# TRS_Jack_Breakout.net
KiCad netlist of a schematic drawn in EAGLE
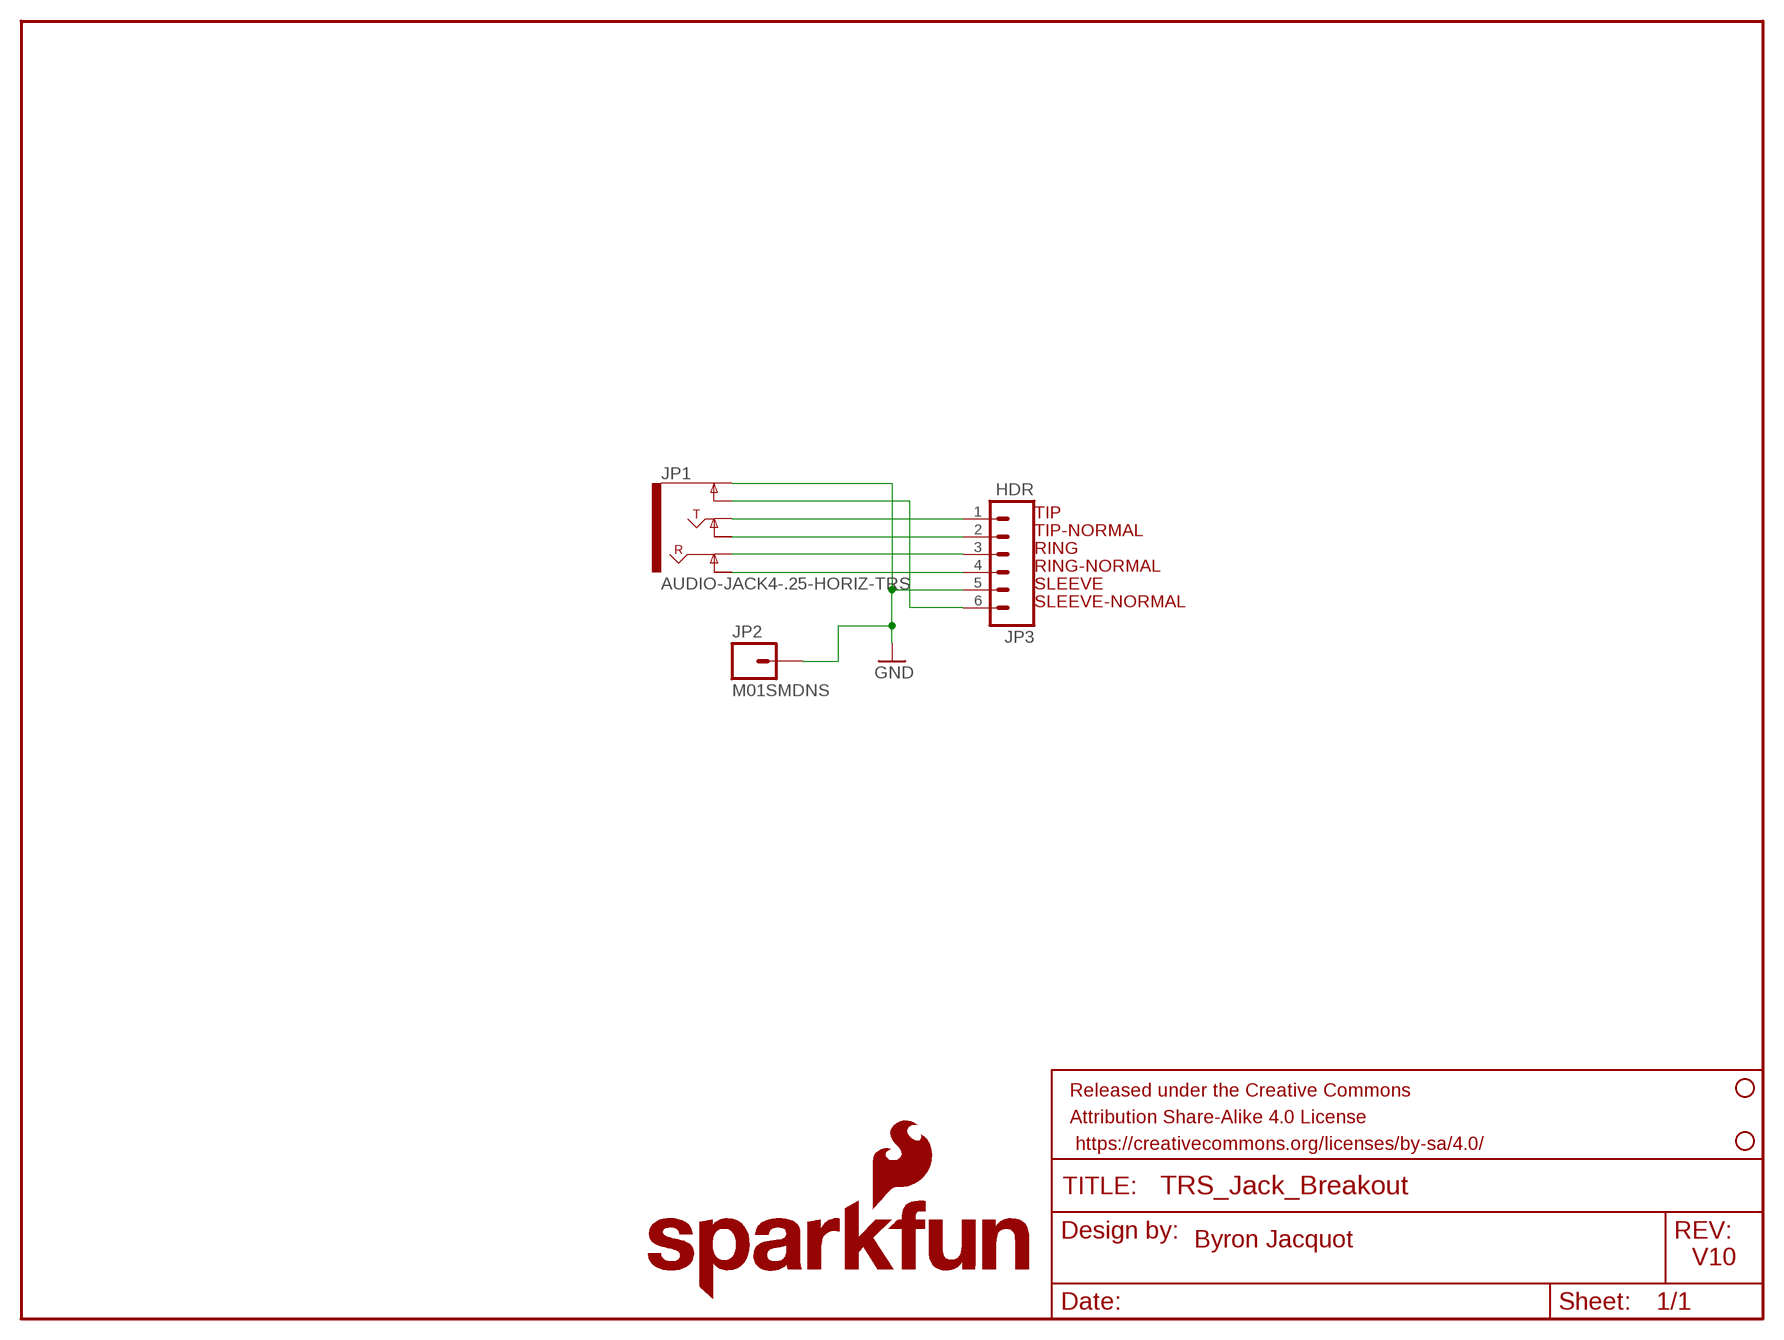
[diagram p0: schematic, sheet 1]

(export (version "E")
  (design (tool "Eeschema 10.0.6"))
  (components
    (comp (ref "FRAME1")
      (value "FRAME-LETTER")
      (footprint "eagle-import:CREATIVE_COMMONS")
      (libsource (lib "eagle-import") (part "FRAME-LETTER"))
    )
    (comp (ref "JP1")
      (value "AUDIO-JACK4-.25-HORIZ-TRS")
      (footprint "eagle-import:AUDIO-JACK-.25-INCH-HORIZ-PTH")
      (libsource (lib "eagle-import") (part "AUDIO-JACK4-.25-HORIZ-TRS"))
    )
    (comp (ref "JP2")
      (value "M01SMDNS")
      (footprint "eagle-import:1X01NS")
      (libsource (lib "eagle-import") (part "M01SMDNS"))
    )
    (comp (ref "JP3")
      (value "HDR")
      (footprint "eagle-import:1X06_NO_SILK")
      (libsource (lib "eagle-import") (part "M06NO_SILK"))
    )
    (comp (ref "LOGO1")
      (value "SFE_LOGO_NAME_FLAME.1_INCH")
      (footprint "eagle-import:SFE_LOGO_NAME_FLAME_.1")
      (libsource (lib "eagle-import") (part "SFE_LOGO_NAME_FLAME.1_INCH"))
    )
    (comp (ref "STANDOFF1")
      (value "STAND-OFF")
      (footprint "eagle-import:STAND-OFF")
      (libsource (lib "eagle-import") (part "STAND-OFF"))
    )
    (comp (ref "STANDOFF2")
      (value "STAND-OFF")
      (footprint "eagle-import:STAND-OFF")
      (libsource (lib "eagle-import") (part "STAND-OFF"))
    )
  )
  (nets
    (net (code "1") (name "GND") (class "Default")
      (node (ref "JP1") (pin "SLEEVE") (pinfunction "EARTH_SLEEVE") (pintype "bidirectional"))
      (node (ref "JP2") (pin "1") (pinfunction "1_1") (pintype "passive"))
      (node (ref "JP3") (pin "5") (pinfunction "5_5") (pintype "passive"))
    )
    (net (code "2") (name "Net-(JP1-EARTH-NORM)") (class "Default")
      (node (ref "JP1") (pin "SLEEVE-NORM") (pinfunction "EARTH-NORM_SLEEVE-NORM") (pintype "bidirectional"))
      (node (ref "JP3") (pin "6") (pinfunction "6_6") (pintype "passive"))
    )
    (net (code "3") (name "Net-(JP1-PadRING)") (class "Default")
      (node (ref "JP1") (pin "RING") (pinfunction "RING_RING") (pintype "bidirectional"))
      (node (ref "JP3") (pin "3") (pinfunction "3_3") (pintype "passive"))
    )
    (net (code "4") (name "Net-(JP1-PadRING-NORM)") (class "Default")
      (node (ref "JP1") (pin "RING-NORM") (pinfunction "RING-NORM_RING-NORM") (pintype "bidirectional"))
      (node (ref "JP3") (pin "4") (pinfunction "4_4") (pintype "passive"))
    )
    (net (code "5") (name "Net-(JP1-PadTIP)") (class "Default")
      (node (ref "JP1") (pin "TIP") (pinfunction "TIP_TIP") (pintype "bidirectional"))
      (node (ref "JP3") (pin "1") (pinfunction "1_1") (pintype "passive"))
    )
    (net (code "6") (name "Net-(JP1-PadTIP-NORM)") (class "Default")
      (node (ref "JP1") (pin "TIP-NORM") (pinfunction "TIP-NORM_TIP-NORM") (pintype "bidirectional"))
      (node (ref "JP3") (pin "2") (pinfunction "2_2") (pintype "passive"))
    )
  )
)
